# LED_Driver.net
KiCad netlist of a schematic drawn in EAGLE
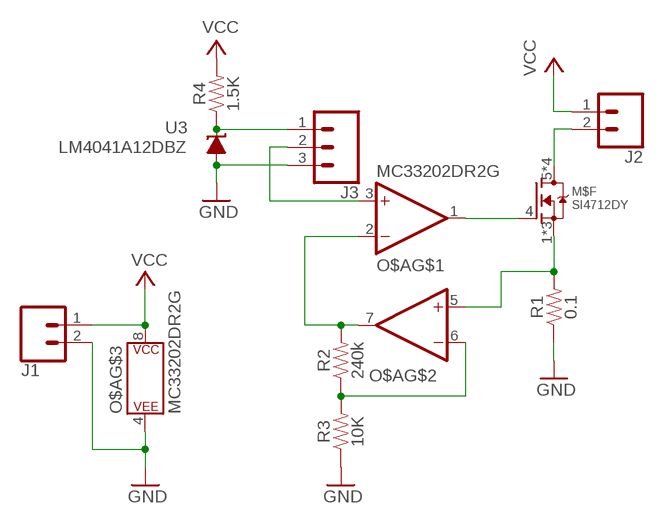
[diagram p0: schematic, sheet 1]

(export (version "E")
  (design (tool "Eeschema 10.0.6"))
  (components
    (comp (ref "J1")
      (value "CONN_02PTH4")
      (footprint "eagle-import:1X02_XTRA_BIG")
      (libsource (lib "eagle-import") (part "CONN_02PTH4"))
    )
    (comp (ref "J2")
      (value "CONN_02PTH4")
      (footprint "eagle-import:1X02_XTRA_BIG")
      (libsource (lib "eagle-import") (part "CONN_02PTH4"))
    )
    (comp (ref "J3")
      (value "CONN_03")
      (footprint "eagle-import:1X03")
      (libsource (lib "eagle-import") (part "CONN_03"))
    )
    (comp (ref "M$F")
      (value "SI4712DY")
      (footprint "eagle-import:SO8")
      (libsource (lib "eagle-import") (part "SI4712DY"))
    )
    (comp (ref "O$A")
      (value "MC33202DR2G")
      (footprint "eagle-import:SOIC8")
      (libsource (lib "eagle-import") (part "MC33202DR2G"))
    )
    (comp (ref "R1")
      (value "0.1")
      (footprint "eagle-import:1210")
      (libsource (lib "eagle-import") (part "0.1OHM-1210-1/2W-1%"))
    )
    (comp (ref "R2")
      (value "240k")
      (footprint "eagle-import:0603")
      (libsource (lib "eagle-import") (part "1.20KOHM-0603-1/10W-1%"))
    )
    (comp (ref "R3")
      (value "10K")
      (footprint "eagle-import:0603")
      (libsource (lib "eagle-import") (part "1.20KOHM-0603-1/10W-1%"))
    )
    (comp (ref "R4")
      (value "1.5K")
      (footprint "eagle-import:0603")
      (libsource (lib "eagle-import") (part "1.20KOHM-0603-1/10W-1%"))
    )
    (comp (ref "U3")
      (value "LM4041A12DBZ")
      (footprint "eagle-import:DBZ_R-PDSO-G3")
      (fields (field (name "MPN") "LM4041A12IDBZR"))
      (libsource (lib "eagle-import") (part "LM4041DBZA12"))
    )
  )
  (nets
    (net (code "1") (name "GND") (class "Default")
      (node (ref "J1") (pin "2") (pinfunction "2_2") (pintype "passive"))
      (node (ref "J3") (pin "3") (pinfunction "3_3") (pintype "passive"))
      (node (ref "O$A") (pin "4") (pinfunction "P$V-_4") (pintype "bidirectional"))
      (node (ref "R1") (pin "1") (pinfunction "1_1") (pintype "passive"))
      (node (ref "R3") (pin "1") (pinfunction "1_1") (pintype "passive"))
      (node (ref "U3") (pin "2") (pinfunction "A_2") (pintype "passive"))
    )
    (net (code "2") (name "Net-(J2-Pad2)") (class "Default")
      (node (ref "J2") (pin "2") (pinfunction "2_2") (pintype "passive"))
      (node (ref "M$F") (pin "5") (pinfunction "D_5") (pintype "bidirectional"))
      (node (ref "M$F") (pin "6") (pinfunction "D_6") (pintype "bidirectional"))
      (node (ref "M$F") (pin "7") (pinfunction "D_7") (pintype "bidirectional"))
      (node (ref "M$F") (pin "8") (pinfunction "D_8") (pintype "bidirectional"))
    )
    (net (code "3") (name "Net-(M$F-G)") (class "Default")
      (node (ref "M$F") (pin "4") (pinfunction "G_4") (pintype "bidirectional"))
      (node (ref "O$A") (pin "1") (pinfunction "OUT_1") (pintype "output"))
    )
    (net (code "4") (name "Net-(O$AA-+IN)") (class "Default")
      (node (ref "J3") (pin "2") (pinfunction "2_2") (pintype "passive"))
      (node (ref "O$A") (pin "3") (pinfunction "+IN_3") (pintype "input"))
    )
    (net (code "5") (name "Net-(O$AA--IN)") (class "Default")
      (node (ref "O$A") (pin "2") (pinfunction "-IN_2") (pintype "input"))
      (node (ref "O$A") (pin "7") (pinfunction "OUT_7") (pintype "output"))
      (node (ref "R2") (pin "2") (pinfunction "2_2") (pintype "passive"))
    )
    (net (code "6") (name "Net-(O$AB-+IN)") (class "Default")
      (node (ref "M$F") (pin "1") (pinfunction "S_1") (pintype "bidirectional"))
      (node (ref "M$F") (pin "2") (pinfunction "S_2") (pintype "bidirectional"))
      (node (ref "M$F") (pin "3") (pinfunction "S_3") (pintype "bidirectional"))
      (node (ref "O$A") (pin "5") (pinfunction "+IN_5") (pintype "input"))
      (node (ref "R1") (pin "2") (pinfunction "2_2") (pintype "passive"))
    )
    (net (code "7") (name "Net-(O$AB--IN)") (class "Default")
      (node (ref "O$A") (pin "6") (pinfunction "-IN_6") (pintype "input"))
      (node (ref "R2") (pin "1") (pinfunction "1_1") (pintype "passive"))
      (node (ref "R3") (pin "2") (pinfunction "2_2") (pintype "passive"))
    )
    (net (code "8") (name "Net-(U3-C)") (class "Default")
      (node (ref "J3") (pin "1") (pinfunction "1_1") (pintype "passive"))
      (node (ref "R4") (pin "1") (pinfunction "1_1") (pintype "passive"))
      (node (ref "U3") (pin "1") (pinfunction "C_1") (pintype "passive"))
    )
    (net (code "9") (name "VCC") (class "Default")
      (node (ref "J1") (pin "1") (pinfunction "1_1") (pintype "passive"))
      (node (ref "J2") (pin "1") (pinfunction "1_1") (pintype "passive"))
      (node (ref "O$A") (pin "8") (pinfunction "P$V+_8") (pintype "bidirectional"))
      (node (ref "R4") (pin "2") (pinfunction "2_2") (pintype "passive"))
    )
  )
)
